# Receiver_s_Circuit.net
KiCad netlist of a schematic drawn in EAGLE
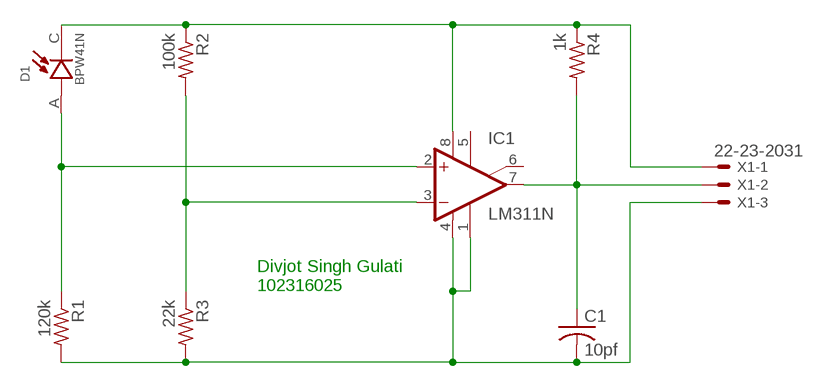
[diagram p0: schematic, sheet 1]

(export (version "E")
  (design (tool "Eeschema 10.0.6"))
  (components
    (comp (ref "C1")
      (value "10pf")
      (footprint "eagle-import:C025-024X044")
      (libsource (lib "eagle-import") (part "C-US025-024X044"))
    )
    (comp (ref "D1")
      (value "BPW41N")
      (footprint "eagle-import:DIO_BPW41N")
      (fields (field (name "MF") "Vishay Semiconductor Opto Division"))
      (libsource (lib "eagle-import") (part "BPW41N"))
    )
    (comp (ref "IC1")
      (value "LM311N")
      (footprint "eagle-import:DIL08")
      (libsource (lib "eagle-import") (part "LM311N"))
    )
    (comp (ref "R1")
      (value "120k")
      (footprint "eagle-import:0204_5")
      (libsource (lib "eagle-import") (part "R-US_0204/5"))
    )
    (comp (ref "R2")
      (value "100k")
      (footprint "eagle-import:0204_5")
      (libsource (lib "eagle-import") (part "R-US_0204/5"))
    )
    (comp (ref "R3")
      (value "22k")
      (footprint "eagle-import:0204_5")
      (libsource (lib "eagle-import") (part "R-US_0204/5"))
    )
    (comp (ref "R4")
      (value "1k")
      (footprint "eagle-import:0204_5")
      (libsource (lib "eagle-import") (part "R-US_0204/5"))
    )
    (comp (ref "X1")
      (value "22-23-2031")
      (footprint "eagle-import:22-23-2031")
      (fields (field (name "MF") "MOLEX"))
      (libsource (lib "eagle-import") (part "22-23-2031"))
    )
  )
  (nets
    (net (code "1") (name "Net-(IC1-+IN)") (class "Default")
      (node (ref "D1") (pin "A") (pinfunction "A_A") (pintype "passive"))
      (node (ref "IC1") (pin "2") (pinfunction "+IN_2") (pintype "input"))
      (node (ref "R1") (pin "1") (pinfunction "1_1") (pintype "passive"))
    )
    (net (code "2") (name "Net-(IC1--IN)") (class "Default")
      (node (ref "IC1") (pin "3") (pinfunction "-IN_3") (pintype "input"))
      (node (ref "R2") (pin "2") (pinfunction "2_2") (pintype "passive"))
      (node (ref "R3") (pin "1") (pinfunction "1_1") (pintype "passive"))
    )
    (net (code "3") (name "Net-(IC1-GND)") (class "Default")
      (node (ref "C1") (pin "2") (pinfunction "2_2") (pintype "passive"))
      (node (ref "IC1") (pin "1") (pinfunction "GND_1") (pintype "passive"))
      (node (ref "IC1") (pin "4") (pinfunction "V-_4") (pintype "power_in"))
      (node (ref "R1") (pin "2") (pinfunction "2_2") (pintype "passive"))
      (node (ref "R3") (pin "2") (pinfunction "2_2") (pintype "passive"))
      (node (ref "X1") (pin "3") (pinfunction "S_3") (pintype "passive"))
    )
    (net (code "4") (name "Net-(IC1-OUT)") (class "Default")
      (node (ref "C1") (pin "1") (pinfunction "1_1") (pintype "passive"))
      (node (ref "IC1") (pin "7") (pinfunction "OUT_7") (pintype "output"))
      (node (ref "R4") (pin "2") (pinfunction "2_2") (pintype "passive"))
      (node (ref "X1") (pin "2") (pinfunction "S_2") (pintype "passive"))
    )
    (net (code "5") (name "Net-(IC1-V+)") (class "Default")
      (node (ref "D1") (pin "C") (pinfunction "C_C") (pintype "passive"))
      (node (ref "IC1") (pin "8") (pinfunction "V+_8") (pintype "power_in"))
      (node (ref "R2") (pin "1") (pinfunction "1_1") (pintype "passive"))
      (node (ref "R4") (pin "1") (pinfunction "1_1") (pintype "passive"))
      (node (ref "X1") (pin "1") (pinfunction "S_1") (pintype "passive"))
    )
    (net (code "6") (name "unconnected-(IC1-ON-Pad5)") (class "Default")
      (node (ref "IC1") (pin "5") (pinfunction "ON_5") (pintype "passive"))
    )
    (net (code "7") (name "unconnected-(IC1-ON{slash}STR-Pad6)") (class "Default")
      (node (ref "IC1") (pin "6") (pinfunction "ON/STR_6") (pintype "passive"))
    )
  )
)
